# 2021-01-21_HALO_ToF_Board-Autorouted.net
KiCad netlist of a schematic drawn in EAGLE
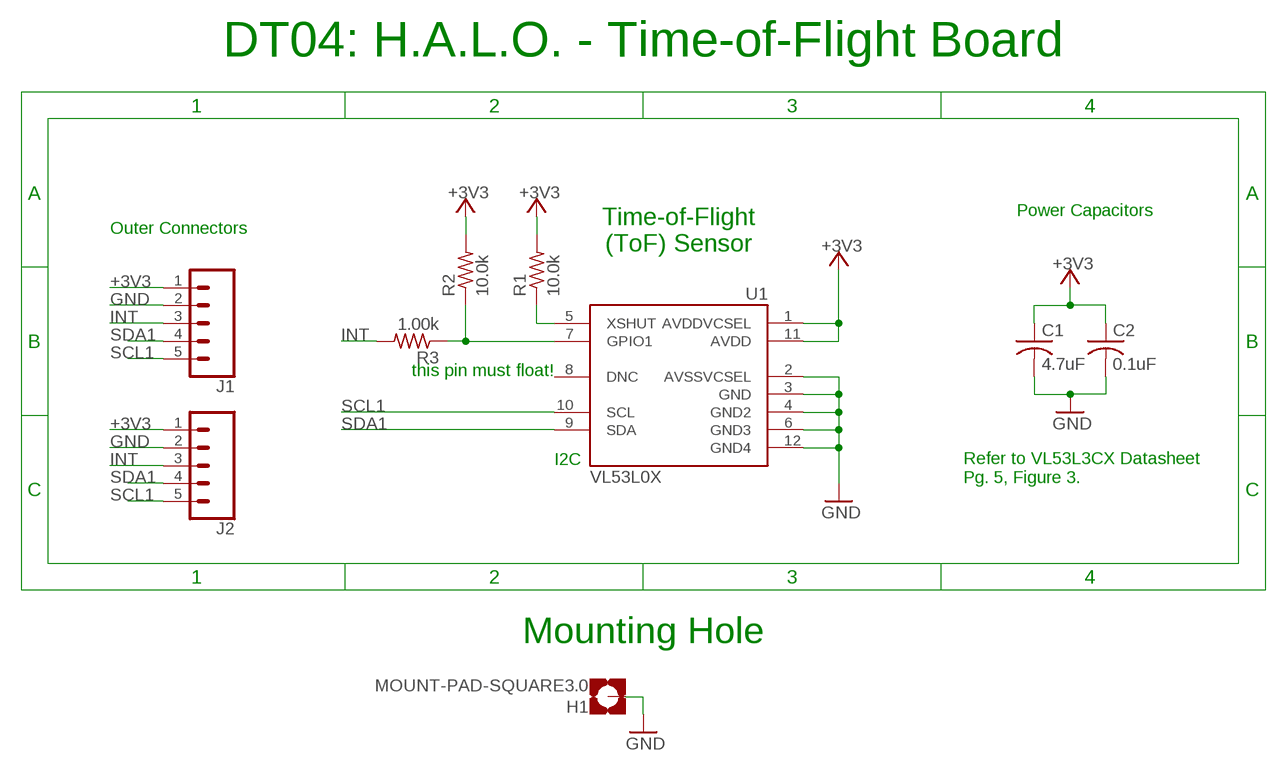
[diagram p0: schematic, sheet 1]

(export (version "E")
  (design (tool "Eeschema 10.0.6"))
  (components
    (comp (ref "C1")
      (value "4.7uF")
      (footprint "eagle-import:C0805")
      (libsource (lib "eagle-import") (part "C-USC0805"))
    )
    (comp (ref "C2")
      (value "0.1uF")
      (footprint "eagle-import:C0805")
      (libsource (lib "eagle-import") (part "C-USC0805"))
    )
    (comp (ref "H1")
      (value "MOUNT-PAD-SQUARE3.0")
      (footprint "eagle-import:3,0-PAD-SQUARE")
      (libsource (lib "eagle-import") (part "MOUNT-PAD-SQUARE3.0"))
    )
    (comp (ref "J1")
      (value "CONN_05")
      (footprint "eagle-import:1X05")
      (libsource (lib "eagle-import") (part "CONN_05"))
    )
    (comp (ref "J2")
      (value "CONN_05")
      (footprint "eagle-import:1X05")
      (libsource (lib "eagle-import") (part "CONN_05"))
    )
    (comp (ref "R1")
      (value "10.0k")
      (footprint "eagle-import:R0805")
      (libsource (lib "eagle-import") (part "R-US_R0805"))
    )
    (comp (ref "R2")
      (value "10.0k")
      (footprint "eagle-import:R0805")
      (libsource (lib "eagle-import") (part "R-US_R0805"))
    )
    (comp (ref "R3")
      (value "1.00k")
      (footprint "eagle-import:R0805")
      (libsource (lib "eagle-import") (part "R-US_R0805"))
    )
    (comp (ref "U1")
      (value "VL53L0X")
      (footprint "eagle-import:VL53L0X")
      (fields (field (name "PARTNO") "AS-ITM-00338"))
      (libsource (lib "eagle-import") (part "AS-ITM-00338"))
    )
  )
  (nets
    (net (code "1") (name "+3V3") (class "Default")
      (node (ref "C1") (pin "1") (pinfunction "1_1") (pintype "passive"))
      (node (ref "C2") (pin "1") (pinfunction "1_1") (pintype "passive"))
      (node (ref "J1") (pin "1") (pinfunction "1_1") (pintype "passive"))
      (node (ref "J2") (pin "1") (pinfunction "1_1") (pintype "passive"))
      (node (ref "R1") (pin "2") (pinfunction "2_2") (pintype "passive"))
      (node (ref "R2") (pin "2") (pinfunction "2_2") (pintype "passive"))
      (node (ref "U1") (pin "1") (pinfunction "AVDDVCSEL_1") (pintype "bidirectional"))
      (node (ref "U1") (pin "11") (pinfunction "AVDD_11") (pintype "bidirectional"))
    )
    (net (code "2") (name "/INT") (class "Default")
      (node (ref "J1") (pin "3") (pinfunction "3_3") (pintype "passive"))
      (node (ref "J2") (pin "3") (pinfunction "3_3") (pintype "passive"))
      (node (ref "R3") (pin "2") (pinfunction "2_2") (pintype "passive"))
    )
    (net (code "3") (name "/SCL1") (class "Default")
      (node (ref "J1") (pin "5") (pinfunction "5_5") (pintype "passive"))
      (node (ref "J2") (pin "5") (pinfunction "5_5") (pintype "passive"))
      (node (ref "U1") (pin "10") (pinfunction "SCL_10") (pintype "bidirectional"))
    )
    (net (code "4") (name "/SDA1") (class "Default")
      (node (ref "J1") (pin "4") (pinfunction "4_4") (pintype "passive"))
      (node (ref "J2") (pin "4") (pinfunction "4_4") (pintype "passive"))
      (node (ref "U1") (pin "9") (pinfunction "SDA_9") (pintype "bidirectional"))
    )
    (net (code "5") (name "GND") (class "Default")
      (node (ref "C1") (pin "2") (pinfunction "2_2") (pintype "passive"))
      (node (ref "C2") (pin "2") (pinfunction "2_2") (pintype "passive"))
      (node (ref "H1") (pin "B3,0") (pinfunction "MOUNT_B3,0") (pintype "passive"))
      (node (ref "J1") (pin "2") (pinfunction "2_2") (pintype "passive"))
      (node (ref "J2") (pin "2") (pinfunction "2_2") (pintype "passive"))
      (node (ref "U1") (pin "12") (pinfunction "GND4_12") (pintype "bidirectional"))
      (node (ref "U1") (pin "2") (pinfunction "AVSSVCSEL_2") (pintype "bidirectional"))
      (node (ref "U1") (pin "3") (pinfunction "GND_3") (pintype "bidirectional"))
      (node (ref "U1") (pin "4") (pinfunction "GND2_4") (pintype "bidirectional"))
      (node (ref "U1") (pin "6") (pinfunction "GND3_6") (pintype "bidirectional"))
    )
    (net (code "6") (name "Net-(U1-GPIO1)") (class "Default")
      (node (ref "R2") (pin "1") (pinfunction "1_1") (pintype "passive"))
      (node (ref "R3") (pin "1") (pinfunction "1_1") (pintype "passive"))
      (node (ref "U1") (pin "7") (pinfunction "GPIO1_7") (pintype "bidirectional"))
    )
    (net (code "7") (name "Net-(U1-XSHUT)") (class "Default")
      (node (ref "R1") (pin "1") (pinfunction "1_1") (pintype "passive"))
      (node (ref "U1") (pin "5") (pinfunction "XSHUT_5") (pintype "bidirectional"))
    )
    (net (code "8") (name "unconnected-(U1-DNC-Pad8)") (class "Default")
      (node (ref "U1") (pin "8") (pinfunction "DNC_8") (pintype "bidirectional"))
    )
  )
)
